# Flight_Controller_Iter2.net
KiCad netlist of a schematic drawn in EAGLE
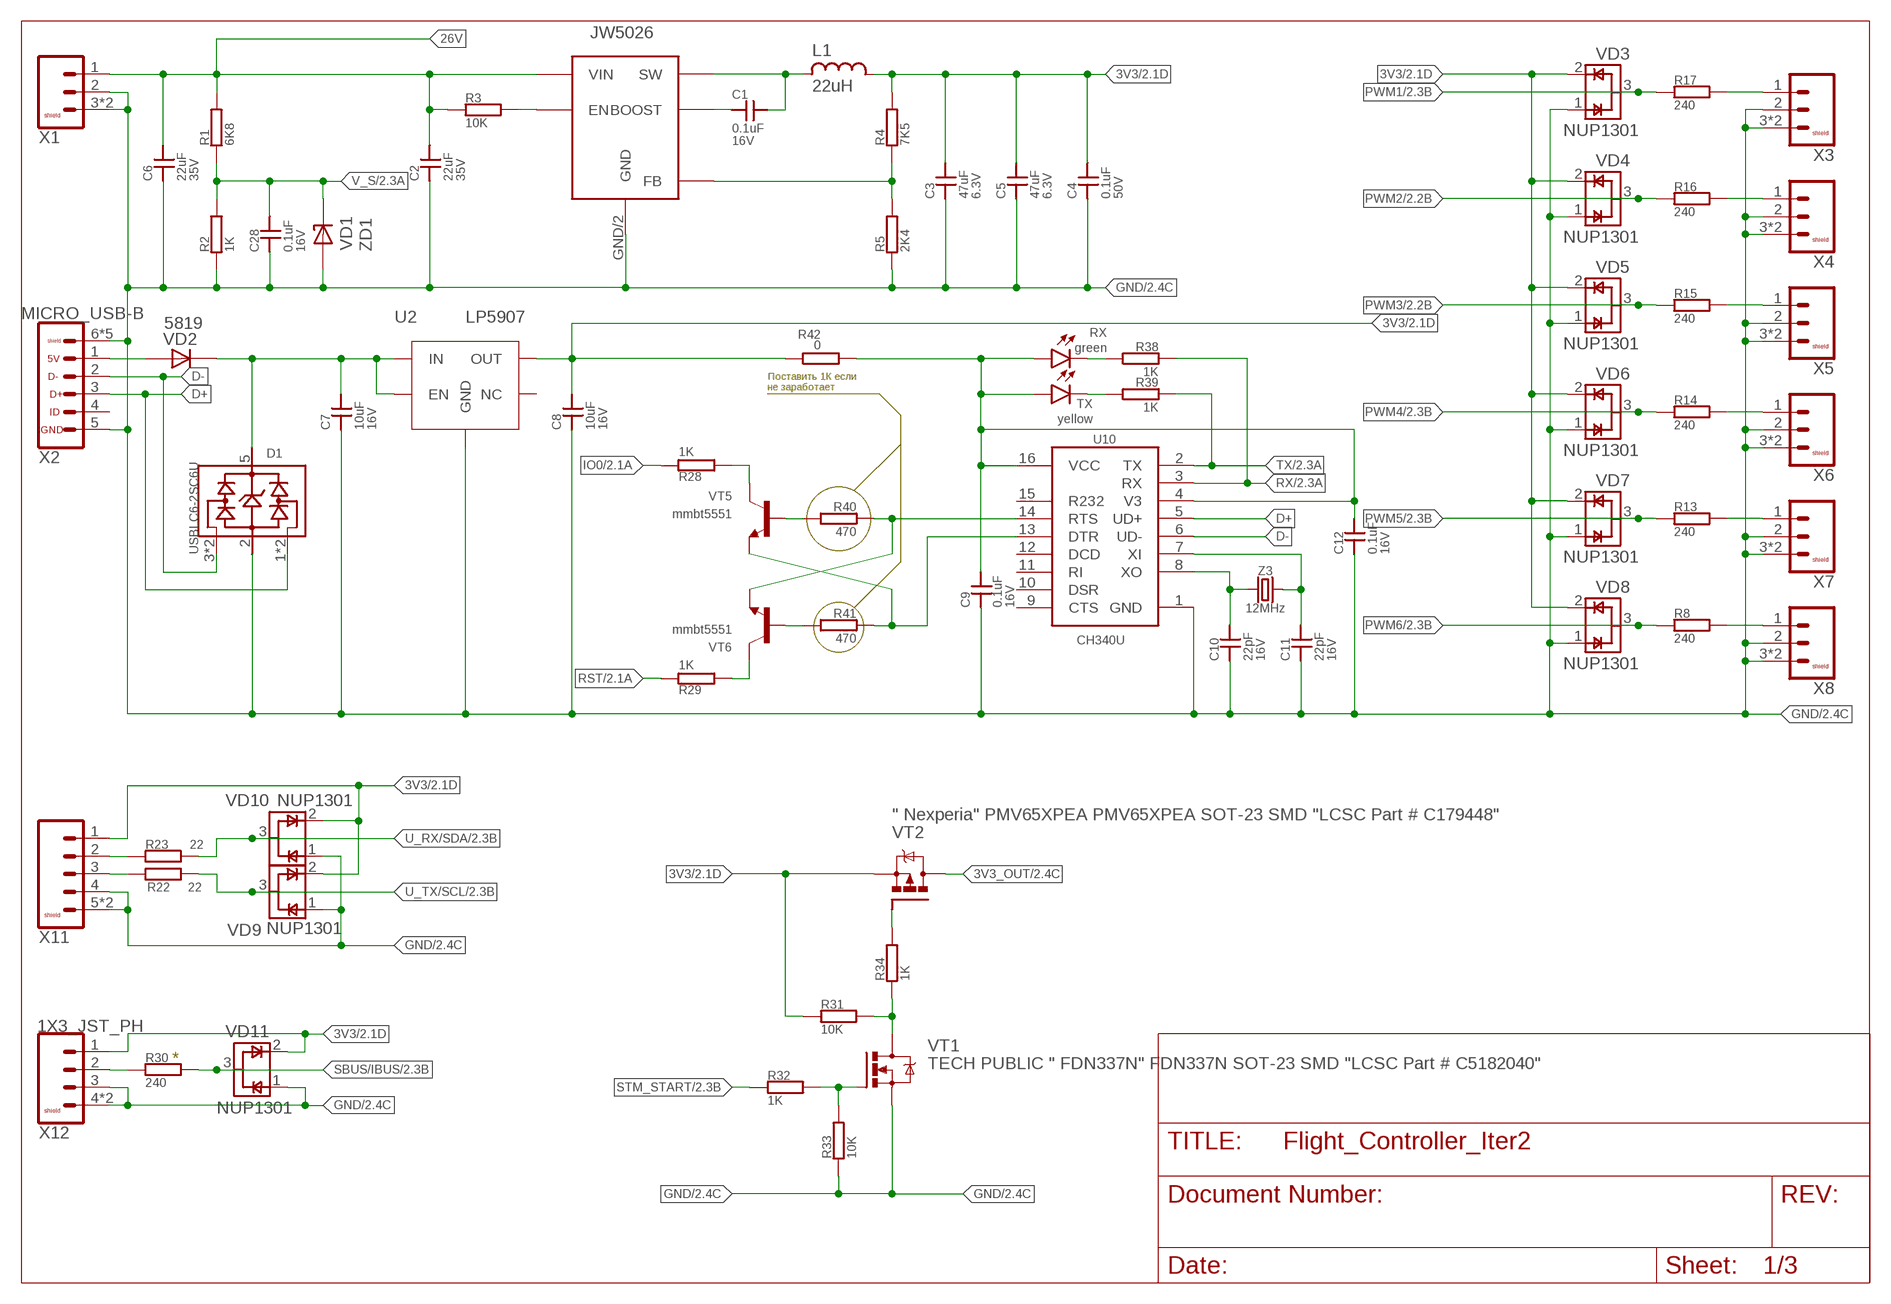
[diagram p0: schematic, sheet 1]
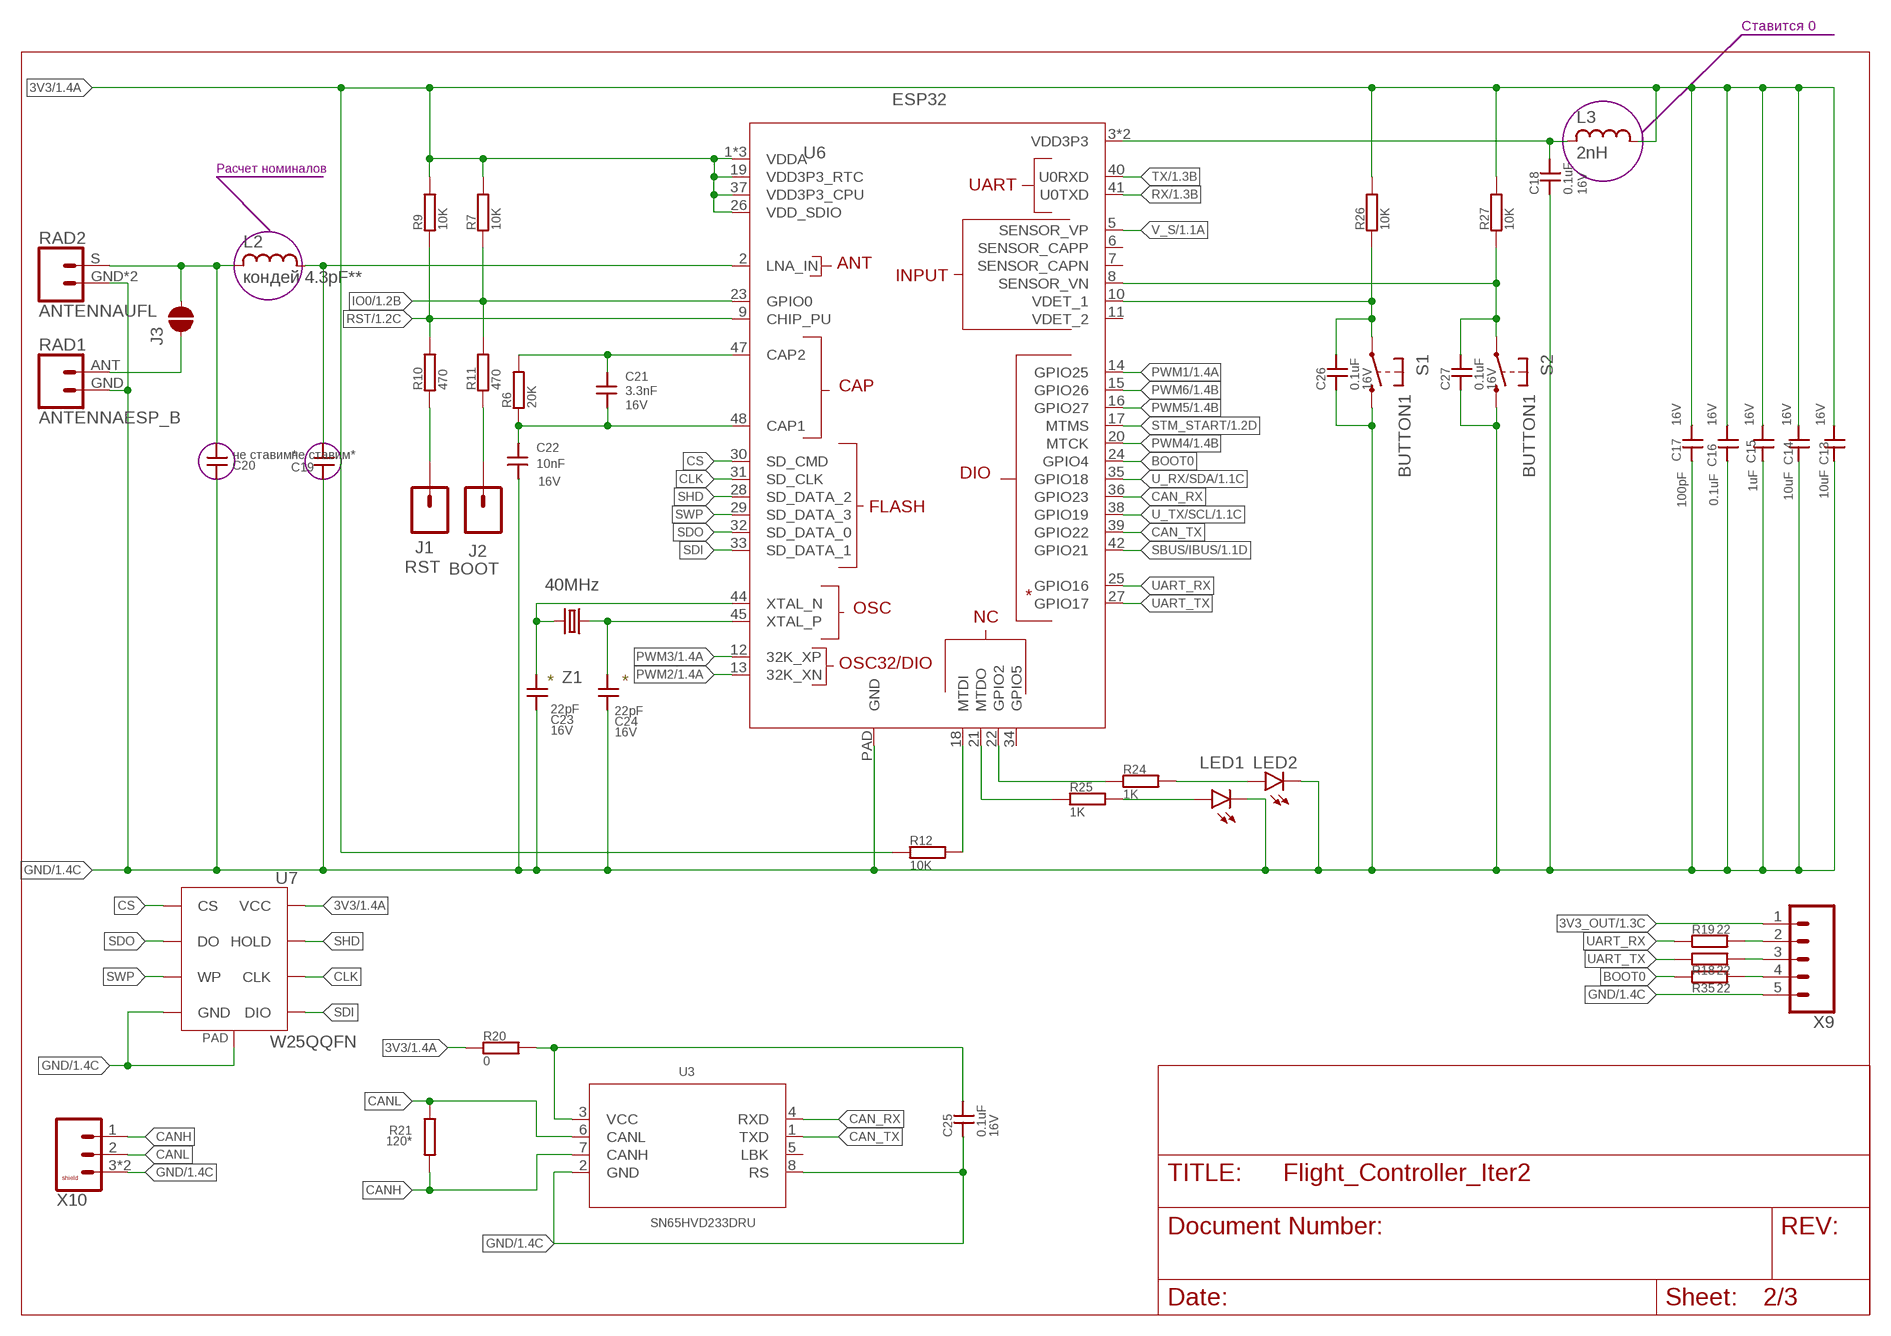
[diagram p1: schematic, sheet 2]

(export (version "E")
  (design (tool "Eeschema 10.0.6"))
  (components
    (comp (ref "C1")
      (value "0.1uF")
      (footprint "eagle-import:0402")
      (fields (field (name "VOLTAGE") "16V"))
      (libsource (lib "eagle-import") (part "C0402"))
    )
    (comp (ref "C2")
      (value "22uF")
      (footprint "eagle-import:0805")
      (fields (field (name "VOLTAGE") "35V"))
      (libsource (lib "eagle-import") (part "C0805"))
    )
    (comp (ref "C3")
      (value "47uF")
      (footprint "eagle-import:0603_SMALL")
      (fields (field (name "VOLTAGE") "6.3V"))
      (libsource (lib "eagle-import") (part "C0603_SMALL"))
    )
    (comp (ref "C4")
      (value "0.1uF")
      (footprint "eagle-import:0603_SMALL")
      (fields (field (name "VOLTAGE") "50V"))
      (libsource (lib "eagle-import") (part "C0603_SMALL"))
    )
    (comp (ref "C5")
      (value "47uF")
      (footprint "eagle-import:0603_SMALL")
      (fields (field (name "VOLTAGE") "6.3V"))
      (libsource (lib "eagle-import") (part "C0603_SMALL"))
    )
    (comp (ref "C6")
      (value "22uF")
      (footprint "eagle-import:0805")
      (fields (field (name "VOLTAGE") "35V"))
      (libsource (lib "eagle-import") (part "C0805"))
    )
    (comp (ref "C7")
      (value "10uF")
      (footprint "eagle-import:0402")
      (fields (field (name "VOLTAGE") "16V"))
      (libsource (lib "eagle-import") (part "C0402"))
    )
    (comp (ref "C8")
      (value "10uF")
      (footprint "eagle-import:0402")
      (fields (field (name "VOLTAGE") "16V"))
      (libsource (lib "eagle-import") (part "C0402"))
    )
    (comp (ref "C9")
      (value "0.1uF")
      (footprint "eagle-import:0402")
      (fields (field (name "VOLTAGE") "16V"))
      (libsource (lib "eagle-import") (part "C0402"))
    )
    (comp (ref "C10")
      (value "22pF")
      (footprint "eagle-import:0402")
      (fields (field (name "VOLTAGE") "16V"))
      (libsource (lib "eagle-import") (part "C0402"))
    )
    (comp (ref "C11")
      (value "22pF")
      (footprint "eagle-import:0402")
      (fields (field (name "VOLTAGE") "16V"))
      (libsource (lib "eagle-import") (part "C0402"))
    )
    (comp (ref "C12")
      (value "0.1uF")
      (footprint "eagle-import:0402")
      (fields (field (name "VOLTAGE") "16V"))
      (libsource (lib "eagle-import") (part "C0402"))
    )
    (comp (ref "C28")
      (value "0.1uF")
      (footprint "eagle-import:0402")
      (fields (field (name "VOLTAGE") "16V"))
      (libsource (lib "eagle-import") (part "C0402"))
    )
    (comp (ref "D1")
      (value "USBLC6-2SC6U")
      (footprint "eagle-import:SOT23-6")
      (libsource (lib "eagle-import") (part "USBLC6-2SC6U"))
    )
    (comp (ref "L1")
      (value "22uH")
      (footprint "eagle-import:0420CDMC")
      (libsource (lib "eagle-import") (part "INDUCTOR0420CDMC"))
    )
    (comp (ref "R1")
      (value "6K8")
      (footprint "eagle-import:0402")
      (libsource (lib "eagle-import") (part "R0402"))
    )
    (comp (ref "R2")
      (value "1K")
      (footprint "eagle-import:0402")
      (libsource (lib "eagle-import") (part "R0402"))
    )
    (comp (ref "R3")
      (value "10K")
      (footprint "eagle-import:0402")
      (libsource (lib "eagle-import") (part "R0402"))
    )
    (comp (ref "R4")
      (value "7K5")
      (footprint "eagle-import:0402")
      (libsource (lib "eagle-import") (part "R0402"))
    )
    (comp (ref "R5")
      (value "2K4")
      (footprint "eagle-import:0402")
      (libsource (lib "eagle-import") (part "R0402"))
    )
    (comp (ref "R8")
      (value "240")
      (footprint "eagle-import:0402")
      (libsource (lib "eagle-import") (part "R0402"))
    )
    (comp (ref "R13")
      (value "240")
      (footprint "eagle-import:0402")
      (libsource (lib "eagle-import") (part "R0402"))
    )
    (comp (ref "R14")
      (value "240")
      (footprint "eagle-import:0402")
      (libsource (lib "eagle-import") (part "R0402"))
    )
    (comp (ref "R15")
      (value "240")
      (footprint "eagle-import:0402")
      (libsource (lib "eagle-import") (part "R0402"))
    )
    (comp (ref "R16")
      (value "240")
      (footprint "eagle-import:0402")
      (libsource (lib "eagle-import") (part "R0402"))
    )
    (comp (ref "R17")
      (value "240")
      (footprint "eagle-import:0402")
      (libsource (lib "eagle-import") (part "R0402"))
    )
    (comp (ref "R22")
      (value "22")
      (footprint "eagle-import:0402")
      (libsource (lib "eagle-import") (part "R0402"))
    )
    (comp (ref "R23")
      (value "22")
      (footprint "eagle-import:0402")
      (libsource (lib "eagle-import") (part "R0402"))
    )
    (comp (ref "R28")
      (value "1K")
      (footprint "eagle-import:0402")
      (libsource (lib "eagle-import") (part "R0402"))
    )
    (comp (ref "R29")
      (value "1K")
      (footprint "eagle-import:0402")
      (libsource (lib "eagle-import") (part "R0402"))
    )
    (comp (ref "R30")
      (value "240")
      (footprint "eagle-import:0402")
      (libsource (lib "eagle-import") (part "R0402"))
    )
    (comp (ref "R31")
      (value "10K")
      (footprint "eagle-import:0402")
      (libsource (lib "eagle-import") (part "R0402"))
    )
    (comp (ref "R32")
      (value "1K")
      (footprint "eagle-import:0402")
      (libsource (lib "eagle-import") (part "R0402"))
    )
    (comp (ref "R33")
      (value "10K")
      (footprint "eagle-import:0402")
      (libsource (lib "eagle-import") (part "R0402"))
    )
    (comp (ref "R34")
      (value "1K")
      (footprint "eagle-import:0402")
      (libsource (lib "eagle-import") (part "R0402"))
    )
    (comp (ref "R38")
      (value "1K")
      (footprint "eagle-import:0402")
      (libsource (lib "eagle-import") (part "R0402"))
    )
    (comp (ref "R39")
      (value "1K")
      (footprint "eagle-import:0402")
      (libsource (lib "eagle-import") (part "R0402"))
    )
    (comp (ref "R40")
      (value "470")
      (footprint "eagle-import:0402")
      (libsource (lib "eagle-import") (part "R0402"))
    )
    (comp (ref "R41")
      (value "470")
      (footprint "eagle-import:0402")
      (libsource (lib "eagle-import") (part "R0402"))
    )
    (comp (ref "R42")
      (value "0")
      (footprint "eagle-import:0402")
      (libsource (lib "eagle-import") (part "R0402"))
    )
    (comp (ref "RX")
      (value "green")
      (footprint "eagle-import:0603")
      (libsource (lib "eagle-import") (part "LED1608"))
    )
    (comp (ref "TX")
      (value "yellow")
      (footprint "eagle-import:0603")
      (libsource (lib "eagle-import") (part "LED1608"))
    )
    (comp (ref "U1")
      (value "JW5026")
      (footprint "eagle-import:SOT-23-6")
      (libsource (lib "eagle-import") (part "TPS560430"))
    )
    (comp (ref "U2")
      (value "LP5907")
      (footprint "eagle-import:SOT-23-5")
      (libsource (lib "eagle-import") (part "LP5907"))
    )
    (comp (ref "U10")
      (value "CH340U")
      (footprint "eagle-import:SOIC-16")
      (libsource (lib "eagle-import") (part "CH340U"))
    )
    (comp (ref "VD1")
      (value "ZD1")
      (footprint "eagle-import:SOD-323")
      (libsource (lib "eagle-import") (part "ZENER-DIODES"))
    )
    (comp (ref "VD2")
      (value "5819")
      (footprint "eagle-import:SOD-323")
      (libsource (lib "eagle-import") (part "DIODE323"))
    )
    (comp (ref "VD3")
      (value "NUP1301")
      (footprint "eagle-import:SOT23")
      (libsource (lib "eagle-import") (part "ESD_PROTECTIONSOT123"))
    )
    (comp (ref "VD4")
      (value "NUP1301")
      (footprint "eagle-import:SOT23")
      (libsource (lib "eagle-import") (part "ESD_PROTECTIONSOT123"))
    )
    (comp (ref "VD5")
      (value "NUP1301")
      (footprint "eagle-import:SOT23")
      (libsource (lib "eagle-import") (part "ESD_PROTECTIONSOT123"))
    )
    (comp (ref "VD6")
      (value "NUP1301")
      (footprint "eagle-import:SOT23")
      (libsource (lib "eagle-import") (part "ESD_PROTECTIONSOT123"))
    )
    (comp (ref "VD7")
      (value "NUP1301")
      (footprint "eagle-import:SOT23")
      (libsource (lib "eagle-import") (part "ESD_PROTECTIONSOT123"))
    )
    (comp (ref "VD8")
      (value "NUP1301")
      (footprint "eagle-import:SOT23")
      (libsource (lib "eagle-import") (part "ESD_PROTECTIONSOT123"))
    )
    (comp (ref "VD9")
      (value "NUP1301")
      (footprint "eagle-import:SOT23")
      (libsource (lib "eagle-import") (part "ESD_PROTECTIONSOT123"))
    )
    (comp (ref "VD10")
      (value "NUP1301")
      (footprint "eagle-import:SOT23")
      (libsource (lib "eagle-import") (part "ESD_PROTECTIONSOT123"))
    )
    (comp (ref "VD11")
      (value "NUP1301")
      (footprint "eagle-import:SOT23")
      (libsource (lib "eagle-import") (part "ESD_PROTECTIONSOT123"))
    )
    (comp (ref "VT1")
      (value "TECH PUBLIC \" FDN337N\" FDN337N SOT-23 SMD \"LCSC Part # C5182040\"")
      (footprint "eagle-import:SOT-23")
      (libsource (lib "eagle-import") (part "N-CANNELSOT-23"))
    )
    (comp (ref "VT2")
      (value "\" Nexperia\" PMV65XPEA PMV65XPEA SOT-23 SMD \"LCSC Part # C179448\"")
      (footprint "eagle-import:SOT-23")
      (libsource (lib "eagle-import") (part "P-CANNELSOT-23"))
    )
    (comp (ref "VT5")
      (value "mmbt5551")
      (footprint "eagle-import:SOT-23")
      (libsource (lib "eagle-import") (part "NPNSOT-23"))
    )
    (comp (ref "VT6")
      (value "mmbt5551")
      (footprint "eagle-import:SOT-23")
      (libsource (lib "eagle-import") (part "NPNSOT-23"))
    )
    (comp (ref "X1")
      (value "1X2_JST_PH_LF2")
      (footprint "eagle-import:JST-PH-SM2-(LF)")
      (libsource (lib "eagle-import") (part "1X2_JST_PH_LF2"))
    )
    (comp (ref "X2")
      (value "MICRO_USB-B")
      (footprint "eagle-import:1981584-1")
      (libsource (lib "eagle-import") (part "MICRO_USB-B"))
    )
    (comp (ref "X3")
      (value "1X2_JST_PH_LF2")
      (footprint "eagle-import:JST-PH-SM2-(LF)")
      (libsource (lib "eagle-import") (part "1X2_JST_PH_LF2"))
    )
    (comp (ref "X4")
      (value "1X2_JST_PH_LF2")
      (footprint "eagle-import:JST-PH-SM2-(LF)")
      (libsource (lib "eagle-import") (part "1X2_JST_PH_LF2"))
    )
    (comp (ref "X5")
      (value "1X2_JST_PH_LF2")
      (footprint "eagle-import:JST-PH-SM2-(LF)")
      (libsource (lib "eagle-import") (part "1X2_JST_PH_LF2"))
    )
    (comp (ref "X6")
      (value "1X2_JST_PH_LF2")
      (footprint "eagle-import:JST-PH-SM2-(LF)")
      (libsource (lib "eagle-import") (part "1X2_JST_PH_LF2"))
    )
    (comp (ref "X7")
      (value "1X2_JST_PH_LF2")
      (footprint "eagle-import:JST-PH-SM2-(LF)")
      (libsource (lib "eagle-import") (part "1X2_JST_PH_LF2"))
    )
    (comp (ref "X8")
      (value "1X2_JST_PH_LF2")
      (footprint "eagle-import:JST-PH-SM2-(LF)")
      (libsource (lib "eagle-import") (part "1X2_JST_PH_LF2"))
    )
    (comp (ref "X11")
      (value "1X4_JST_PH_2JST_PH_SM4_2MM(LF)")
      (footprint "eagle-import:JST-PH-SM4-(LF)")
      (libsource (lib "eagle-import") (part "1X4_JST_PH_2JST_PH_SM4_2MM(LF)"))
    )
    (comp (ref "X12")
      (value "1X3_JST_PH")
      (footprint "eagle-import:JST-PH-SM3-(LF)")
      (libsource (lib "eagle-import") (part "1X3_JST_PH"))
    )
    (comp (ref "Z3")
      (value "12MHz")
      (footprint "eagle-import:CRYSTAL-SMD-3.2X2.5MM")
      (libsource (lib "eagle-import") (part "CRYSTAL4FOOT"))
    )
    (comp (ref "C13")
      (value "10uF")
      (footprint "eagle-import:0402")
      (fields (field (name "VOLTAGE") "16V"))
      (libsource (lib "eagle-import") (part "C0402"))
    )
    (comp (ref "C14")
      (value "10uF")
      (footprint "eagle-import:0402")
      (fields (field (name "VOLTAGE") "16V"))
      (libsource (lib "eagle-import") (part "C0402"))
    )
    (comp (ref "C15")
      (value "1uF")
      (footprint "eagle-import:0402")
      (fields (field (name "VOLTAGE") "16V"))
      (libsource (lib "eagle-import") (part "C0402"))
    )
    (comp (ref "C16")
      (value "0.1uF")
      (footprint "eagle-import:0402")
      (fields (field (name "VOLTAGE") "16V"))
      (libsource (lib "eagle-import") (part "C0402"))
    )
    (comp (ref "C17")
      (value "100pF")
      (footprint "eagle-import:0402")
      (fields (field (name "VOLTAGE") "16V"))
      (libsource (lib "eagle-import") (part "C0402"))
    )
    (comp (ref "C18")
      (value "0.1uF")
      (footprint "eagle-import:0402")
      (fields (field (name "VOLTAGE") "16V"))
      (libsource (lib "eagle-import") (part "C0402"))
    )
    (comp (ref "C19")
      (value "не ставим*")
      (footprint "eagle-import:0402")
      (libsource (lib "eagle-import") (part "C0402"))
    )
    (comp (ref "C20")
      (value "не ставим*")
      (footprint "eagle-import:0402")
      (libsource (lib "eagle-import") (part "C0402"))
    )
    (comp (ref "C21")
      (value "3.3nF")
      (footprint "eagle-import:0402")
      (fields (field (name "VOLTAGE") "16V"))
      (libsource (lib "eagle-import") (part "C0402"))
    )
    (comp (ref "C22")
      (value "10nF")
      (footprint "eagle-import:0402")
      (fields (field (name "VOLTAGE") "16V"))
      (libsource (lib "eagle-import") (part "C0402"))
    )
    (comp (ref "C23")
      (value "22pF")
      (footprint "eagle-import:0402")
      (fields (field (name "VOLTAGE") "16V"))
      (libsource (lib "eagle-import") (part "C0402"))
    )
    (comp (ref "C24")
      (value "22pF")
      (footprint "eagle-import:0402")
      (fields (field (name "VOLTAGE") "16V"))
      (libsource (lib "eagle-import") (part "C0402"))
    )
    (comp (ref "C25")
      (value "0.1uF")
      (footprint "eagle-import:0402")
      (fields (field (name "VOLTAGE") "16V"))
      (libsource (lib "eagle-import") (part "C0402"))
    )
    (comp (ref "C26")
      (value "0.1uF")
      (footprint "eagle-import:0402")
      (fields (field (name "VOLTAGE") "16V"))
      (libsource (lib "eagle-import") (part "C0402"))
    )
    (comp (ref "C27")
      (value "0.1uF")
      (footprint "eagle-import:0402")
      (fields (field (name "VOLTAGE") "16V"))
      (libsource (lib "eagle-import") (part "C0402"))
    )
    (comp (ref "J1")
      (value "RST")
      (footprint "eagle-import:1X1_PAD_T")
      (libsource (lib "eagle-import") (part "1X1_PAD1X1PAD"))
    )
    (comp (ref "J2")
      (value "BOOT")
      (footprint "eagle-import:1X1_PAD_T")
      (libsource (lib "eagle-import") (part "1X1_PAD1X1PAD"))
    )
    (comp (ref "J3")
      (value "TEST_PAD1X1MM")
      (footprint "eagle-import:TEST_PAD")
      (libsource (lib "eagle-import") (part "TEST_PAD1X1MM"))
    )
    (comp (ref "L2")
      (value "кондей 4.3pF**")
      (footprint "eagle-import:0402")
      (libsource (lib "eagle-import") (part "L0402"))
    )
    (comp (ref "L3")
      (value "2nH")
      (footprint "eagle-import:0402")
      (libsource (lib "eagle-import") (part "L0402"))
    )
    (comp (ref "LED1")
      (value "LED0402")
      (footprint "eagle-import:0402")
      (libsource (lib "eagle-import") (part "LED0402"))
    )
    (comp (ref "LED2")
      (value "LED0402")
      (footprint "eagle-import:0402")
      (libsource (lib "eagle-import") (part "LED0402"))
    )
    (comp (ref "R6")
      (value "20K")
      (footprint "eagle-import:0402")
      (libsource (lib "eagle-import") (part "R0402"))
    )
    (comp (ref "R7")
      (value "10K")
      (footprint "eagle-import:0402")
      (libsource (lib "eagle-import") (part "R0402"))
    )
    (comp (ref "R9")
      (value "10K")
      (footprint "eagle-import:0402")
      (libsource (lib "eagle-import") (part "R0402"))
    )
    (comp (ref "R10")
      (value "470")
      (footprint "eagle-import:0402")
      (libsource (lib "eagle-import") (part "R0402"))
    )
    (comp (ref "R11")
      (value "470")
      (footprint "eagle-import:0402")
      (libsource (lib "eagle-import") (part "R0402"))
    )
    (comp (ref "R12")
      (value "10K")
      (footprint "eagle-import:0402")
      (libsource (lib "eagle-import") (part "R0402"))
    )
    (comp (ref "R18")
      (value "22")
      (footprint "eagle-import:0402")
      (libsource (lib "eagle-import") (part "R0402"))
    )
    (comp (ref "R19")
      (value "22")
      (footprint "eagle-import:0402")
      (libsource (lib "eagle-import") (part "R0402"))
    )
    (comp (ref "R20")
      (value "0")
      (footprint "eagle-import:0402")
      (libsource (lib "eagle-import") (part "R0402"))
    )
    (comp (ref "R21")
      (value "120*")
      (footprint "eagle-import:0603_SMALL")
      (libsource (lib "eagle-import") (part "R0603_SMALL"))
    )
    (comp (ref "R24")
      (value "1K")
      (footprint "eagle-import:0402")
      (libsource (lib "eagle-import") (part "R0402"))
    )
    (comp (ref "R25")
      (value "1K")
      (footprint "eagle-import:0402")
      (libsource (lib "eagle-import") (part "R0402"))
    )
    (comp (ref "R26")
      (value "10K")
      (footprint "eagle-import:0402")
      (libsource (lib "eagle-import") (part "R0402"))
    )
    (comp (ref "R27")
      (value "10K")
      (footprint "eagle-import:0402")
      (libsource (lib "eagle-import") (part "R0402"))
    )
    (comp (ref "R35")
      (value "22")
      (footprint "eagle-import:0402")
      (libsource (lib "eagle-import") (part "R0402"))
    )
    (comp (ref "RAD1")
      (value "ANTENNAESP_B")
      (footprint "eagle-import:2.4GHZB")
      (libsource (lib "eagle-import") (part "ANTENNAESP_B"))
    )
    (comp (ref "RAD2")
      (value "ANTENNAUFL")
      (footprint "eagle-import:U.FL")
      (libsource (lib "eagle-import") (part "ANTENNAUFL"))
    )
    (comp (ref "S1")
      (value "BUTTON1")
      (footprint "eagle-import:3X4X2")
      (libsource (lib "eagle-import") (part "BUTTON1"))
    )
    (comp (ref "S2")
      (value "BUTTON1")
      (footprint "eagle-import:3X4X2")
      (libsource (lib "eagle-import") (part "BUTTON1"))
    )
    (comp (ref "U3")
      (value "SN65HVD233DRU")
      (footprint "eagle-import:SOIC-8")
      (libsource (lib "eagle-import") (part "SN65HVD233DRU"))
    )
    (comp (ref "U6")
      (value "ESP32")
      (footprint "eagle-import:QFN48(5X5MM)")
      (libsource (lib "eagle-import") (part "ESP32"))
    )
    (comp (ref "U7")
      (value "W25QQFN")
      (footprint "eagle-import:WSON8X6-MM")
      (libsource (lib "eagle-import") (part "W25QQFN"))
    )
    (comp (ref "X9")
      (value "1X5FFC5-1MM")
      (footprint "eagle-import:FFC-1MM_5")
      (libsource (lib "eagle-import") (part "1X5FFC5-1MM"))
    )
    (comp (ref "X10")
      (value "1X2_JST_PH_LF2")
      (footprint "eagle-import:JST-PH-SM2-(LF)")
      (libsource (lib "eagle-import") (part "1X2_JST_PH_LF2"))
    )
    (comp (ref "Z1")
      (value "40MHz")
      (footprint "eagle-import:CRYSTAL-SMD-3.2X2.5MM")
      (libsource (lib "eagle-import") (part "CRYSTAL4FOOT"))
    )
  )
  (nets
    (net (code "1") (name "3V3") (class "Default")
      (node (ref "C13") (pin "2") (pinfunction "P$2_2") (pintype "bidirectional"))
      (node (ref "C14") (pin "2") (pinfunction "P$2_2") (pintype "bidirectional"))
      (node (ref "C15") (pin "2") (pinfunction "P$2_2") (pintype "bidirectional"))
      (node (ref "C16") (pin "2") (pinfunction "P$2_2") (pintype "bidirectional"))
      (node (ref "C17") (pin "2") (pinfunction "P$2_2") (pintype "bidirectional"))
      (node (ref "C3") (pin "P$2") (pinfunction "P$2_P$2") (pintype "bidirectional"))
      (node (ref "C4") (pin "P$2") (pinfunction "P$2_P$2") (pintype "bidirectional"))
      (node (ref "C5") (pin "P$2") (pinfunction "P$2_P$2") (pintype "bidirectional"))
      (node (ref "C8") (pin "2") (pinfunction "P$2_2") (pintype "bidirectional"))
      (node (ref "L1") (pin "2") (pinfunction "2_2") (pintype "passive"))
      (node (ref "L3") (pin "2") (pinfunction "2_2") (pintype "passive"))
      (node (ref "R12") (pin "1") (pinfunction "P$1_1") (pintype "bidirectional"))
      (node (ref "R20") (pin "1") (pinfunction "P$1_1") (pintype "bidirectional"))
      (node (ref "R26") (pin "2") (pinfunction "P$2_2") (pintype "bidirectional"))
      (node (ref "R27") (pin "2") (pinfunction "P$2_2") (pintype "bidirectional"))
      (node (ref "R31") (pin "1") (pinfunction "P$1_1") (pintype "bidirectional"))
      (node (ref "R4") (pin "2") (pinfunction "P$2_2") (pintype "bidirectional"))
      (node (ref "R42") (pin "2") (pinfunction "P$2_2") (pintype "bidirectional"))
      (node (ref "R7") (pin "2") (pinfunction "P$2_2") (pintype "bidirectional"))
      (node (ref "R9") (pin "2") (pinfunction "P$2_2") (pintype "bidirectional"))
      (node (ref "U2") (pin "5") (pinfunction "OUT_5") (pintype "bidirectional"))
      (node (ref "U6") (pin "1") (pinfunction "VDDA_1") (pintype "bidirectional"))
      (node (ref "U6") (pin "19") (pinfunction "VDD3P3_RTC_19") (pintype "bidirectional"))
      (node (ref "U6") (pin "26") (pinfunction "VDD_SDIO_26") (pintype "bidirectional"))
      (node (ref "U6") (pin "37") (pinfunction "VDD3P3_CPU_37") (pintype "bidirectional"))
      (node (ref "U6") (pin "43") (pinfunction "VDDA_43") (pintype "bidirectional"))
      (node (ref "U6") (pin "46") (pinfunction "VDDA_46") (pintype "bidirectional"))
      (node (ref "U7") (pin "P$9") (pinfunction "VCC_P$9") (pintype "bidirectional"))
      (node (ref "VD10") (pin "2") (pinfunction "VCC_2") (pintype "bidirectional"))
      (node (ref "VD11") (pin "2") (pinfunction "VCC_2") (pintype "bidirectional"))
      (node (ref "VD3") (pin "2") (pinfunction "VCC_2") (pintype "bidirectional"))
      (node (ref "VD4") (pin "2") (pinfunction "VCC_2") (pintype "bidirectional"))
      (node (ref "VD5") (pin "2") (pinfunction "VCC_2") (pintype "bidirectional"))
      (node (ref "VD6") (pin "2") (pinfunction "VCC_2") (pintype "bidirectional"))
      (node (ref "VD7") (pin "2") (pinfunction "VCC_2") (pintype "bidirectional"))
      (node (ref "VD8") (pin "2") (pinfunction "VCC_2") (pintype "bidirectional"))
      (node (ref "VD9") (pin "2") (pinfunction "VCC_2") (pintype "bidirectional"))
      (node (ref "VT2") (pin "2") (pinfunction "S_2") (pintype "passive"))
      (node (ref "X11") (pin "1") (pinfunction "1_1") (pintype "passive"))
      (node (ref "X12") (pin "1") (pinfunction "1_1") (pintype "passive"))
    )
    (net (code "2") (name "3V3_OUT") (class "Default")
      (node (ref "VT2") (pin "3") (pinfunction "D_3") (pintype "passive"))
      (node (ref "X9") (pin "1") (pinfunction "1_1") (pintype "passive"))
    )
    (net (code "3") (name "26V") (class "Default")
      (node (ref "C2") (pin "P$2") (pinfunction "P$2_P$2") (pintype "bidirectional"))
      (node (ref "C6") (pin "P$2") (pinfunction "P$2_P$2") (pintype "bidirectional"))
      (node (ref "R1") (pin "2") (pinfunction "P$2_2") (pintype "bidirectional"))
      (node (ref "R3") (pin "1") (pinfunction "P$1_1") (pintype "bidirectional"))
      (node (ref "U1") (pin "IN/5") (pinfunction "VIN_IN/5") (pintype "input"))
      (node (ref "X1") (pin "1") (pinfunction "1_1") (pintype "passive"))
    )
    (net (code "4") (name "BOOT0") (class "Default")
      (node (ref "R35") (pin "1") (pinfunction "P$1_1") (pintype "bidirectional"))
      (node (ref "U6") (pin "24") (pinfunction "GPIO4_24") (pintype "bidirectional"))
    )
    (net (code "5") (name "CANH") (class "Default")
      (node (ref "R21") (pin "P$1") (pinfunction "P$1_P$1") (pintype "bidirectional"))
      (node (ref "U3") (pin "7") (pinfunction "CANH_7") (pintype "bidirectional"))
      (node (ref "X10") (pin "1") (pinfunction "1_1") (pintype "passive"))
    )
    (net (code "6") (name "CANL") (class "Default")
      (node (ref "R21") (pin "P$2") (pinfunction "P$2_P$2") (pintype "bidirectional"))
      (node (ref "U3") (pin "6") (pinfunction "CANL_6") (pintype "bidirectional"))
      (node (ref "X10") (pin "2") (pinfunction "2_2") (pintype "passive"))
    )
    (net (code "7") (name "CAN_RX") (class "Default")
      (node (ref "U3") (pin "4") (pinfunction "RXD_4") (pintype "bidirectional"))
      (node (ref "U6") (pin "36") (pinfunction "GPIO23_36") (pintype "bidirectional"))
    )
    (net (code "8") (name "CAN_TX") (class "Default")
      (node (ref "U3") (pin "1") (pinfunction "TXD_1") (pintype "bidirectional"))
      (node (ref "U6") (pin "39") (pinfunction "GPIO22_39") (pintype "bidirectional"))
    )
    (net (code "9") (name "CLK") (class "Default")
      (node (ref "U6") (pin "31") (pinfunction "SD_CLK_31") (pintype "bidirectional"))
      (node (ref "U7") (pin "P$7") (pinfunction "CLK_P$7") (pintype "bidirectional"))
    )
    (net (code "10") (name "CS") (class "Default")
      (node (ref "U6") (pin "30") (pinfunction "SD_CMD_30") (pintype "bidirectional"))
      (node (ref "U7") (pin "P$2") (pinfunction "CS_P$2") (pintype "bidirectional"))
    )
    (net (code "11") (name "D+") (class "Default")
      (node (ref "D1") (pin "1") (pinfunction "I/O1_1") (pintype "bidirectional"))
      (node (ref "D1") (pin "6") (pinfunction "I/O1_6") (pintype "bidirectional"))
      (node (ref "U10") (pin "5") (pinfunction "UD+_5") (pintype "bidirectional"))
      (node (ref "X2") (pin "3") (pinfunction "D+_3") (pintype "passive"))
    )
    (net (code "12") (name "D-") (class "Default")
      (node (ref "D1") (pin "3") (pinfunction "I/O2_3") (pintype "bidirectional"))
      (node (ref "D1") (pin "4") (pinfunction "I/O2_4") (pintype "bidirectional"))
      (node (ref "U10") (pin "6") (pinfunction "UD-_6") (pintype "bidirectional"))
      (node (ref "X2") (pin "2") (pinfunction "D-_2") (pintype "passive"))
    )
    (net (code "13") (name "GND") (class "Default")
      (node (ref "C10") (pin "1") (pinfunction "P$1_1") (pintype "bidirectional"))
      (node (ref "C11") (pin "1") (pinfunction "P$1_1") (pintype "bidirectional"))
      (node (ref "C12") (pin "1") (pinfunction "P$1_1") (pintype "bidirectional"))
      (node (ref "C13") (pin "1") (pinfunction "P$1_1") (pintype "bidirectional"))
      (node (ref "C14") (pin "1") (pinfunction "P$1_1") (pintype "bidirectional"))
      (node (ref "C15") (pin "1") (pinfunction "P$1_1") (pintype "bidirectional"))
      (node (ref "C16") (pin "1") (pinfunction "P$1_1") (pintype "bidirectional"))
      (node (ref "C17") (pin "1") (pinfunction "P$1_1") (pintype "bidirectional"))
      (node (ref "C18") (pin "1") (pinfunction "P$1_1") (pintype "bidirectional"))
      (node (ref "C19") (pin "1") (pinfunction "P$1_1") (pintype "bidirectional"))
      (node (ref "C2") (pin "P$1") (pinfunction "P$1_P$1") (pintype "bidirectional"))
      (node (ref "C20") (pin "1") (pinfunction "P$1_1") (pintype "bidirectional"))
      (node (ref "C22") (pin "1") (pinfunction "P$1_1") (pintype "bidirectional"))
      (node (ref "C23") (pin "1") (pinfunction "P$1_1") (pintype "bidirectional"))
      (node (ref "C24") (pin "1") (pinfunction "P$1_1") (pintype "bidirectional"))
      (node (ref "C25") (pin "1") (pinfunction "P$1_1") (pintype "bidirectional"))
      (node (ref "C26") (pin "1") (pinfunction "P$1_1") (pintype "bidirectional"))
      (node (ref "C27") (pin "1") (pinfunction "P$1_1") (pintype "bidirectional"))
      (node (ref "C28") (pin "1") (pinfunction "P$1_1") (pintype "bidirectional"))
      (node (ref "C3") (pin "P$1") (pinfunction "P$1_P$1") (pintype "bidirectional"))
      (node (ref "C4") (pin "P$1") (pinfunction "P$1_P$1") (pintype "bidirectional"))
      (node (ref "C5") (pin "P$1") (pinfunction "P$1_P$1") (pintype "bidirectional"))
      (node (ref "C6") (pin "P$1") (pinfunction "P$1_P$1") (pintype "bidirectional"))
      (node (ref "C7") (pin "1") (pinfunction "P$1_1") (pintype "bidirectional"))
      (node (ref "C8") (pin "1") (pinfunction "P$1_1") (pintype "bidirectional"))
      (node (ref "C9") (pin "1") (pinfunction "P$1_1") (pintype "bidirectional"))
      (node (ref "D1") (pin "2") (pinfunction "GND_2") (pintype "power_in"))
      (node (ref "LED1") (pin "1") (pinfunction "C_1") (pintype "passive"))
      (node (ref "LED2") (pin "1") (pinfunction "C_1") (pintype "passive"))
      (node (ref "R2") (pin "1") (pinfunction "P$1_1") (pintype "bidirectional"))
      (node (ref "R33") (pin "1") (pinfunction "P$1_1") (pintype "bidirectional"))
      (node (ref "R5") (pin "1") (pinfunction "P$1_1") (pintype "bidirectional"))
      (node (ref "RAD1") (pin "GND") (pinfunction "GND_GND") (pintype "passive"))
      (node (ref "RAD2") (pin "GND") (pinfunction "GND_GND") (pintype "passive"))
      (node (ref "RAD2") (pin "GND1") (pinfunction "GND_GND1") (pintype "passive"))
      (node (ref "S1") (pin "P$2") (pinfunction "4_P$2") (pintype "passive"))
      (node (ref "S2") (pin "P$2") (pinfunction "4_P$2") (pintype "passive"))
      (node (ref "U1") (pin "GND/2") (pinfunction "GND_GND/2") (pintype "output"))
      (node (ref "U10") (pin "1") (pinfunction "GND_1") (pintype "power_in"))
      (node (ref "U2") (pin "2") (pinfunction "GND_2") (pintype "bidirectional"))
      (node (ref "U3") (pin "2") (pinfunction "GND_2") (pintype "bidirectional"))
      (node (ref "U3") (pin "8") (pinfunction "RS_8") (pintype "bidirectional"))
      (node (ref "U6") (pin "PAD") (pinfunction "GND_PAD") (pintype "bidirectional"))
      (node (ref "U7") (pin "P$1") (pinfunction "P$1_P$1") (pintype "bidirectional"))
      (node (ref "U7") (pin "P$5") (pinfunction "GND_P$5") (pintype "bidirectional"))
      (node (ref "VD1") (pin "1") (pinfunction "A_1") (pintype "passive"))
      (node (ref "VD10") (pin "1") (pinfunction "GND_1") (pintype "bidirectional"))
      (node (ref "VD11") (pin "1") (pinfunction "GND_1") (pintype "bidirectional"))
      (node (ref "VD3") (pin "1") (pinfunction "GND_1") (pintype "bidirectional"))
      (node (ref "VD4") (pin "1") (pinfunction "GND_1") (pintype "bidirectional"))
      (node (ref "VD5") (pin "1") (pinfunction "GND_1") (pintype "bidirectional"))
      (node (ref "VD6") (pin "1") (pinfunction "GND_1") (pintype "bidirectional"))
      (node (ref "VD7") (pin "1") (pinfunction "GND_1") (pintype "bidirectional"))
      (node (ref "VD8") (pin "1") (pinfunction "GND_1") (pintype "bidirectional"))
      (node (ref "VD9") (pin "1") (pinfunction "GND_1") (pintype "bidirectional"))
      (node (ref "VT1") (pin "2") (pinfunction "S_2") (pintype "passive"))
      (node (ref "X1") (pin "2") (pinfunction "2_2") (pintype "passive"))
      (node (ref "X1") (pin "3") (pinfunction "3_3") (pintype "passive"))
      (node (ref "X1") (pin "4") (pinfunction "3_4") (pintype "passive"))
      (node (ref "X10") (pin "3") (pinfunction "3_3") (pintype "passive"))
      (node (ref "X10") (pin "4") (pinfunction "3_4") (pintype "passive"))
      (node (ref "X11") (pin "4") (pinfunction "4_4") (pintype "passive"))
      (node (ref "X11") (pin "5") (pinfunction "5_5") (pintype "passive"))
      (node (ref "X11") (pin "6") (pinfunction "5_6") (pintype "passive"))
      (node (ref "X12") (pin "3") (pinfunction "3_3") (pintype "passive"))
      (node (ref "X12") (pin "4") (pinfunction "4_4") (pintype "passive"))
      (node (ref "X12") (pin "5") (pinfunction "4_5") (pintype "passive"))
      (node (ref "X2") (pin "5") (pinfunction "GND_5") (pintype "passive"))
      (node (ref "X2") (pin "6") (pinfunction "SHIELD_6") (pintype "passive"))
      (node (ref "X2") (pin "P$1") (pinfunction "SHIELD_P$1") (pintype "passive"))
      (node (ref "X2") (pin "P$2") (pinfunction "SHIELD_P$2") (pintype "passive"))
      (node (ref "X2") (pin "P$3") (pinfunction "SHIELD_P$3") (pintype "passive"))
      (node (ref "X2") (pin "P$7") (pinfunction "SHIELD_P$7") (pintype "passive"))
      (node (ref "X3") (pin "2") (pinfunction "2_2") (pintype "passive"))
      (node (ref "X3") (pin "3") (pinfunction "3_3") (pintype "passive"))
      (node (ref "X3") (pin "4") (pinfunction "3_4") (pintype "passive"))
      (node (ref "X4") (pin "2") (pinfunction "2_2") (pintype "passive"))
      (node (ref "X4") (pin "3") (pinfunction "3_3") (pintype "passive"))
      (node (ref "X4") (pin "4") (pinfunction "3_4") (pintype "passive"))
      (node (ref "X5") (pin "2") (pinfunction "2_2") (pintype "passive"))
      (node (ref "X5") (pin "3") (pinfunction "3_3") (pintype "passive"))
      (node (ref "X5") (pin "4") (pinfunction "3_4") (pintype "passive"))
      (node (ref "X6") (pin "2") (pinfunction "2_2") (pintype "passive"))
      (node (ref "X6") (pin "3") (pinfunction "3_3") (pintype "passive"))
      (node (ref "X6") (pin "4") (pinfunction "3_4") (pintype "passive"))
      (node (ref "X7") (pin "2") (pinfunction "2_2") (pintype "passive"))
      (node (ref "X7") (pin "3") (pinfunction "3_3") (pintype "passive"))
      (node (ref "X7") (pin "4") (pinfunction "3_4") (pintype "passive"))
      (node (ref "X8") (pin "2") (pinfunction "2_2") (pintype "passive"))
      (node (ref "X8") (pin "3") (pinfunction "3_3") (pintype "passive"))
      (node (ref "X8") (pin "4") (pinfunction "3_4") (pintype "passive"))
      (node (ref "X9") (pin "5") (pinfunction "5_5") (pintype "passive"))
    )
    (net (code "14") (name "IO0") (class "Default")
      (node (ref "R11") (pin "2") (pinfunction "P$2_2") (pintype "bidirectional"))
      (node (ref "R28") (pin "1") (pinfunction "P$1_1") (pintype "bidirectional"))
      (node (ref "R7") (pin "1") (pinfunction "P$1_1") (pintype "bidirectional"))
      (node (ref "U6") (pin "23") (pinfunction "GPIO0_23") (pintype "bidirectional"))
    )
    (net (code "15") (name "Net-(C1-P$1)") (class "Default")
      (node (ref "C1") (pin "1") (pinfunction "P$1_1") (pintype "bidirectional"))
      (node (ref "U1") (pin "BOOST/1") (pinfunction "BOOST_BOOST/1") (pintype "output"))
    )
    (net (code "16") (name "Net-(C1-P$2)") (class "Default")
      (node (ref "C1") (pin "2") (pinfunction "P$2_2") (pintype "bidirectional"))
      (node (ref "L1") (pin "1") (pinfunction "1_1") (pintype "passive"))
      (node (ref "U1") (pin "SW/6") (pinfunction "SW_SW/6") (pintype "output"))
    )
    (net (code "17") (name "Net-(C7-P$2)") (class "Default")
      (node (ref "C7") (pin "2") (pinfunction "P$2_2") (pintype "bidirectional"))
      (node (ref "D1") (pin "5") (pinfunction "VBUS_5") (pintype "power_in"))
      (node (ref "U2") (pin "1") (pinfunction "IN_1") (pintype "bidirectional"))
      (node (ref "U2") (pin "3") (pinfunction "EN_3") (pintype "bidirectional"))
      (node (ref "VD2") (pin "2") (pinfunction "C_2") (pintype "passive"))
    )
    (net (code "18") (name "Net-(C10-P$2)") (class "Default")
      (node (ref "C10") (pin "2") (pinfunction "P$2_2") (pintype "bidirectional"))
      (node (ref "U10") (pin "8") (pinfunction "XO_8") (pintype "output"))
      (node (ref "Z3") (pin "3") (pinfunction "2_3") (pintype "passive"))
    )
    (net (code "19") (name "Net-(C11-P$2)") (class "Default")
      (node (ref "C11") (pin "2") (pinfunction "P$2_2") (pintype "bidirectional"))
      (node (ref "U10") (pin "7") (pinfunction "XI_7") (pintype "input"))
      (node (ref "Z3") (pin "1") (pinfunction "1_1") (pintype "passive"))
    )
    (net (code "20") (name "Net-(C12-P$2)") (class "Default")
      (node (ref "C12") (pin "2") (pinfunction "P$2_2") (pintype "bidirectional"))
      (node (ref "C9") (pin "2") (pinfunction "P$2_2") (pintype "bidirectional"))
      (node (ref "R42") (pin "1") (pinfunction "P$1_1") (pintype "bidirectional"))
      (node (ref "RX") (pin "P$2") (pinfunction "A_P$2") (pintype "passive"))
      (node (ref "TX") (pin "P$2") (pinfunction "A_P$2") (pintype "passive"))
      (node (ref "U10") (pin "16") (pinfunction "VCC_16") (pintype "power_in"))
      (node (ref "U10") (pin "4") (pinfunction "V3_4") (pintype "power_in"))
    )
    (net (code "21") (name "Net-(C18-P$2)") (class "Default")
      (node (ref "C18") (pin "2") (pinfunction "P$2_2") (pintype "bidirectional"))
      (node (ref "L3") (pin "1") (pinfunction "1_1") (pintype "passive"))
      (node (ref "U6") (pin "3") (pinfunction "VDD3P3_3") (pintype "bidirectional"))
      (node (ref "U6") (pin "4") (pinfunction "VDD3P3_4") (pintype "bidirectional"))
    )
    (net (code "22") (name "Net-(C19-P$2)") (class "Default")
      (node (ref "C19") (pin "2") (pinfunction "P$2_2") (pintype "bidirectional"))
      (node (ref "L2") (pin "2") (pinfunction "2_2") (pintype "passive"))
      (node (ref "U6") (pin "2") (pinfunction "LNA_IN_2") (pintype "bidirectional"))
    )
    (net (code "23") (name "Net-(C20-P$2)") (class "Default")
      (node (ref "C20") (pin "2") (pinfunction "P$2_2") (pintype "bidirectional"))
      (node (ref "J3") (pin "P$2") (pinfunction "P$2_P$2") (pintype "bidirectional"))
      (node (ref "L2") (pin "1") (pinfunction "1_1") (pintype "passive"))
      (node (ref "RAD2") (pin "S") (pinfunction "ANTENNA_S") (pintype "passive"))
    )
    (net (code "24") (name "Net-(C21-P$1)") (class "Default")
      (node (ref "C21") (pin "1") (pinfunction "P$1_1") (pintype "bidirectional"))
      (node (ref "C22") (pin "2") (pinfunction "P$2_2") (pintype "bidirectional"))
      (node (ref "R6") (pin "1") (pinfunction "P$1_1") (pintype "bidirectional"))
      (node (ref "U6") (pin "48") (pinfunction "CAP1_48") (pintype "bidirectional"))
    )
    (net (code "25") (name "Net-(C21-P$2)") (class "Default")
      (node (ref "C21") (pin "2") (pinfunction "P$2_2") (pintype "bidirectional"))
      (node (ref "R6") (pin "2") (pinfunction "P$2_2") (pintype "bidirectional"))
      (node (ref "U6") (pin "47") (pinfunction "CAP2_47") (pintype "bidirectional"))
    )
    (net (code "26") (name "Net-(C23-P$2)") (class "Default")
      (node (ref "C23") (pin "2") (pinfunction "P$2_2") (pintype "bidirectional"))
      (node (ref "U6") (pin "44") (pinfunction "XTAL_N_44") (pintype "bidirectional"))
      (node (ref "Z1") (pin "3") (pinfunction "2_3") (pintype "passive"))
    )
    (net (code "27") (name "Net-(C24-P$2)") (class "Default")
      (node (ref "C24") (pin "2") (pinfunction "P$2_2") (pintype "bidirectional"))
      (node (ref "U6") (pin "45") (pinfunction "XTAL_P_45") (pintype "bidirectional"))
      (node (ref "Z1") (pin "1") (pinfunction "1_1") (pintype "passive"))
    )
    (net (code "28") (name "Net-(C25-P$2)") (class "Default")
      (node (ref "C25") (pin "2") (pinfunction "P$2_2") (pintype "bidirectional"))
      (node (ref "R20") (pin "2") (pinfunction "P$2_2") (pintype "bidirectional"))
      (node (ref "U3") (pin "3") (pinfunction "VCC_3") (pintype "bidirectional"))
    )
    (net (code "29") (name "Net-(C26-P$2)") (class "Default")
      (node (ref "C26") (pin "2") (pinfunction "P$2_2") (pintype "bidirectional"))
      (node (ref "R26") (pin "1") (pinfunction "P$1_1") (pintype "bidirectional"))
      (node (ref "S1") (pin "P$1") (pinfunction "3_P$1") (pintype "passive"))
      (node (ref "U6") (pin "10") (pinfunction "VDET_1_10") (pintype "bidirectional"))
    )
    (net (code "30") (name "Net-(C27-P$2)") (class "Default")
      (node (ref "C27") (pin "2") (pinfunction "P$2_2") (pintype "bidirectional"))
      (node (ref "R27") (pin "1") (pinfunction "P$1_1") (pintype "bidirectional"))
      (node (ref "S2") (pin "P$1") (pinfunction "3_P$1") (pintype "passive"))
      (node (ref "U6") (pin "8") (pinfunction "SENSOR_VN_8") (pintype "bidirectional"))
    )
    (net (code "31") (name "Net-(J1-1)") (class "Default")
      (node (ref "J1") (pin "P$1") (pinfunction "1_P$1") (pintype "passive"))
      (node (ref "R10") (pin "1") (pinfunction "P$1_1") (pintype "bidirectional"))
    )
    (net (code "32") (name "Net-(J2-1)") (class "Default")
      (node (ref "J2") (pin "P$1") (pinfunction "1_P$1") (pintype "passive"))
      (node (ref "R11") (pin "1") (pinfunction "P$1_1") (pintype "bidirectional"))
    )
    (net (code "33") (name "Net-(LED1-A)") (class "Default")
      (node (ref "LED1") (pin "2") (pinfunction "A_2") (pintype "passive"))
      (node (ref "R25") (pin "2") (pinfunction "P$2_2") (pintype "bidirectional"))
    )
    (net (code "34") (name "Net-(LED2-A)") (class "Default")
      (node (ref "LED2") (pin "2") (pinfunction "A_2") (pintype "passive"))
      (node (ref "R24") (pin "2") (pinfunction "P$2_2") (pintype "bidirectional"))
    )
    (net (code "35") (name "Net-(R3-P$2)") (class "Default")
      (node (ref "R3") (pin "2") (pinfunction "P$2_2") (pintype "bidirectional"))
      (node (ref "U1") (pin "EN/4") (pinfunction "EN_EN/4") (pintype "input"))
    )
    (net (code "36") (name "Net-(R4-P$1)") (class "Default")
      (node (ref "R4") (pin "1") (pinfunction "P$1_1") (pintype "bidirectional"))
      (node (ref "R5") (pin "2") (pinfunction "P$2_2") (pintype "bidirectional"))
      (node (ref "U1") (pin "FB/3") (pinfunction "FB_FB/3") (pintype "input"))
    )
    (net (code "37") (name "Net-(R8-P$2)") (class "Default")
      (node (ref "R8") (pin "2") (pinfunction "P$2_2") (pintype "bidirectional"))
      (node (ref "X8") (pin "1") (pinfunction "1_1") (pintype "passive"))
    )
    (net (code "38") (name "Net-(R12-P$2)") (class "Default")
      (node (ref "R12") (pin "2") (pinfunction "P$2_2") (pintype "bidirectional"))
      (node (ref "U6") (pin "18") (pinfunction "MTDI_18") (pintype "bidirectional"))
    )
    (net (code "39") (name "Net-(R13-P$2)") (class "Default")
      (node (ref "R13") (pin "2") (pinfunction "P$2_2") (pintype "bidirectional"))
      (node (ref "X7") (pin "1") (pinfunction "1_1") (pintype "passive"))
    )
    (net (code "40") (name "Net-(R14-P$2)") (class "Default")
      (node (ref "R14") (pin "2") (pinfunction "P$2_2") (pintype "bidirectional"))
      (node (ref "X6") (pin "1") (pinfunction "1_1") (pintype "passive"))
    )
    (net (code "41") (name "Net-(R15-P$2)") (class "Default")
      (node (ref "R15") (pin "2") (pinfunction "P$2_2") (pintype "bidirectional"))
      (node (ref "X5") (pin "1") (pinfunction "1_1") (pintype "passive"))
    )
    (net (code "42") (name "Net-(R16-P$2)") (class "Default")
      (node (ref "R16") (pin "2") (pinfunction "P$2_2") (pintype "bidirectional"))
      (node (ref "X4") (pin "1") (pinfunction "1_1") (pintype "passive"))
    )
    (net (code "43") (name "Net-(R17-P$2)") (class "Default")
      (node (ref "R17") (pin "2") (pinfunction "P$2_2") (pintype "bidirectional"))
      (node (ref "X3") (pin "1") (pinfunction "1_1") (pintype "passive"))
    )
    (net (code "44") (name "Net-(R18-P$2)") (class "Default")
      (node (ref "R18") (pin "2") (pinfunction "P$2_2") (pintype "bidirectional"))
      (node (ref "X9") (pin "3") (pinfunction "3_3") (pintype "passive"))
    )
    (net (code "45") (name "Net-(R19-P$2)") (class "Default")
      (node (ref "R19") (pin "2") (pinfunction "P$2_2") (pintype "bidirectional"))
      (node (ref "X9") (pin "2") (pinfunction "2_2") (pintype "passive"))
    )
    (net (code "46") (name "Net-(R22-P$1)") (class "Default")
      (node (ref "R22") (pin "1") (pinfunction "P$1_1") (pintype "bidirectional"))
      (node (ref "X11") (pin "3") (pinfunction "3_3") (pintype "passive"))
    )
    (net (code "47") (name "Net-(R23-P$1)") (class "Default")
      (node (ref "R23") (pin "1") (pinfunction "P$1_1") (pintype "bidirectional"))
      (node (ref "X11") (pin "2") (pinfunction "2_2") (pintype "passive"))
    )
    (net (code "48") (name "Net-(R24-P$1)") (class "Default")
      (node (ref "R24") (pin "1") (pinfunction "P$1_1") (pintype "bidirectional"))
      (node (ref "U6") (pin "22") (pinfunction "GPIO2_22") (pintype "bidirectional"))
    )
    (net (code "49") (name "Net-(R25-P$1)") (class "Default")
      (node (ref "R25") (pin "1") (pinfunction "P$1_1") (pintype "bidirectional"))
      (node (ref "U6") (pin "21") (pinfunction "MTDO_21") (pintype "bidirectional"))
    )
    (net (code "50") (name "Net-(R28-P$2)") (class "Default")
      (node (ref "R28") (pin "2") (pinfunction "P$2_2") (pintype "bidirectional"))
      (node (ref "VT5") (pin "3") (pinfunction "C_3") (pintype "passive"))
    )
    (net (code "51") (name "Net-(R29-P$2)") (class "Default")
      (node (ref "R29") (pin "2") (pinfunction "P$2_2") (pintype "bidirectional"))
      (node (ref "VT6") (pin "3") (pinfunction "C_3") (pintype "passive"))
    )
    (net (code "52") (name "Net-(R30-P$1)") (class "Default")
      (node (ref "R30") (pin "1") (pinfunction "P$1_1") (pintype "bidirectional"))
      (node (ref "X12") (pin "2") (pinfunction "2_2") (pintype "passive"))
    )
    (net (code "53") (name "Net-(R31-P$2)") (class "Default")
      (node (ref "R31") (pin "2") (pinfunction "P$2_2") (pintype "bidirectional"))
      (node (ref "R34") (pin "1") (pinfunction "P$1_1") (pintype "bidirectional"))
      (node (ref "VT1") (pin "3") (pinfunction "D_3") (pintype "passive"))
    )
    (net (code "54") (name "Net-(R32-P$2)") (class "Default")
      (node (ref "R32") (pin "2") (pinfunction "P$2_2") (pintype "bidirectional"))
      (node (ref "R33") (pin "2") (pinfunction "P$2_2") (pintype "bidirectional"))
      (node (ref "VT1") (pin "1") (pinfunction "G_1") (pintype "passive"))
    )
    (net (code "55") (name "Net-(R34-P$2)") (class "Default")
      (node (ref "R34") (pin "2") (pinfunction "P$2_2") (pintype "bidirectional"))
      (node (ref "VT2") (pin "1") (pinfunction "G_1") (pintype "passive"))
    )
    (net (code "56") (name "Net-(R35-P$2)") (class "Default")
      (node (ref "R35") (pin "2") (pinfunction "P$2_2") (pintype "bidirectional"))
      (node (ref "X9") (pin "4") (pinfunction "4_4") (pintype "passive"))
    )
    (net (code "57") (name "Net-(R38-P$2)") (class "Default")
      (node (ref "R38") (pin "2") (pinfunction "P$2_2") (pintype "bidirectional"))
      (node (ref "RX") (pin "P$1") (pinfunction "C_P$1") (pintype "passive"))
    )
    (net (code "58") (name "Net-(R39-P$2)") (class "Default")
      (node (ref "R39") (pin "2") (pinfunction "P$2_2") (pintype "bidirectional"))
      (node (ref "TX") (pin "P$1") (pinfunction "C_P$1") (pintype "passive"))
    )
    (net (code "59") (name "Net-(R40-P$1)") (class "Default")
      (node (ref "R40") (pin "1") (pinfunction "P$1_1") (pintype "bidirectional"))
      (node (ref "U10") (pin "14") (pinfunction "RTS_14") (pintype "bidirectional"))
      (node (ref "VT6") (pin "2") (pinfunction "E_2") (pintype "passive"))
    )
    (net (code "60") (name "Net-(R40-P$2)") (class "Default")
      (node (ref "R40") (pin "2") (pinfunction "P$2_2") (pintype "bidirectional"))
      (node (ref "VT5") (pin "1") (pinfunction "B_1") (pintype "passive"))
    )
    (net (code "61") (name "Net-(R41-P$1)") (class "Default")
      (node (ref "R41") (pin "1") (pinfunction "P$1_1") (pintype "bidirectional"))
      (node (ref "U10") (pin "13") (pinfunction "DTR_13") (pintype "bidirectional"))
      (node (ref "VT5") (pin "2") (pinfunction "E_2") (pintype "passive"))
    )
    (net (code "62") (name "Net-(R41-P$2)") (class "Default")
      (node (ref "R41") (pin "2") (pinfunction "P$2_2") (pintype "bidirectional"))
      (node (ref "VT6") (pin "1") (pinfunction "B_1") (pintype "passive"))
    )
    (net (code "63") (name "Net-(RAD1-ANTENNA)") (class "Default")
      (node (ref "J3") (pin "P$1") (pinfunction "P$1_P$1") (pintype "bidirectional"))
      (node (ref "RAD1") (pin "ANT") (pinfunction "ANTENNA_ANT") (pintype "passive"))
    )
    (net (code "64") (name "Net-(VD2-A)") (class "Default")
      (node (ref "VD2") (pin "1") (pinfunction "A_1") (pintype "passive"))
      (node (ref "X2") (pin "1") (pinfunction "5V_1") (pintype "passive"))
    )
    (net (code "65") (name "PWM1") (class "Default")
      (node (ref "R17") (pin "1") (pinfunction "P$1_1") (pintype "bidirectional"))
      (node (ref "U6") (pin "14") (pinfunction "GPIO25_14") (pintype "bidirectional"))
      (node (ref "VD3") (pin "3") (pinfunction "I/O_3") (pintype "bidirectional"))
    )
    (net (code "66") (name "PWM2") (class "Default")
      (node (ref "R16") (pin "1") (pinfunction "P$1_1") (pintype "bidirectional"))
      (node (ref "U6") (pin "13") (pinfunction "32K_XN_13") (pintype "bidirectional"))
      (node (ref "VD4") (pin "3") (pinfunction "I/O_3") (pintype "bidirectional"))
    )
    (net (code "67") (name "PWM3") (class "Default")
      (node (ref "R15") (pin "1") (pinfunction "P$1_1") (pintype "bidirectional"))
      (node (ref "U6") (pin "12") (pinfunction "32K_XP_12") (pintype "bidirectional"))
      (node (ref "VD5") (pin "3") (pinfunction "I/O_3") (pintype "bidirectional"))
    )
    (net (code "68") (name "PWM4") (class "Default")
      (node (ref "R14") (pin "1") (pinfunction "P$1_1") (pintype "bidirectional"))
      (node (ref "U6") (pin "20") (pinfunction "MTCK_20") (pintype "bidirectional"))
      (node (ref "VD6") (pin "3") (pinfunction "I/O_3") (pintype "bidirectional"))
    )
    (net (code "69") (name "PWM5") (class "Default")
      (node (ref "R13") (pin "1") (pinfunction "P$1_1") (pintype "bidirectional"))
      (node (ref "U6") (pin "16") (pinfunction "GPIO27_16") (pintype "bidirectional"))
      (node (ref "VD7") (pin "3") (pinfunction "I/O_3") (pintype "bidirectional"))
    )
    (net (code "70") (name "PWM6") (class "Default")
      (node (ref "R8") (pin "1") (pinfunction "P$1_1") (pintype "bidirectional"))
      (node (ref "U6") (pin "15") (pinfunction "GPIO26_15") (pintype "bidirectional"))
      (node (ref "VD8") (pin "3") (pinfunction "I/O_3") (pintype "bidirectional"))
    )
    (net (code "71") (name "RST") (class "Default")
      (node (ref "R10") (pin "2") (pinfunction "P$2_2") (pintype "bidirectional"))
      (node (ref "R29") (pin "1") (pinfunction "P$1_1") (pintype "bidirectional"))
      (node (ref "R9") (pin "1") (pinfunction "P$1_1") (pintype "bidirectional"))
      (node (ref "U6") (pin "9") (pinfunction "CHIP_PU_9") (pintype "bidirectional"))
    )
    (net (code "72") (name "RX") (class "Default")
      (node (ref "R38") (pin "1") (pinfunction "P$1_1") (pintype "bidirectional"))
      (node (ref "U10") (pin "3") (pinfunction "RX_3") (pintype "input"))
      (node (ref "U6") (pin "41") (pinfunction "U0TXD_41") (pintype "bidirectional"))
    )
    (net (code "73") (name "SBUS{slash}IBUS") (class "Default")
      (node (ref "R30") (pin "2") (pinfunction "P$2_2") (pintype "bidirectional"))
      (node (ref "U6") (pin "42") (pinfunction "GPIO21_42") (pintype "bidirectional"))
      (node (ref "VD11") (pin "3") (pinfunction "I/O_3") (pintype "bidirectional"))
    )
    (net (code "74") (name "SDI") (class "Default")
      (node (ref "U6") (pin "33") (pinfunction "SD_DATA_1_33") (pintype "bidirectional"))
      (node (ref "U7") (pin "P$6") (pinfunction "DIO_P$6") (pintype "bidirectional"))
    )
    (net (code "75") (name "SDO") (class "Default")
      (node (ref "U6") (pin "32") (pinfunction "SD_DATA_0_32") (pintype "bidirectional"))
      (node (ref "U7") (pin "P$3") (pinfunction "DO_P$3") (pintype "bidirectional"))
    )
    (net (code "76") (name "SHD") (class "Default")
      (node (ref "U6") (pin "28") (pinfunction "SD_DATA_2_28") (pintype "bidirectional"))
      (node (ref "U7") (pin "P$8") (pinfunction "HOLD_P$8") (pintype "bidirectional"))
    )
    (net (code "77") (name "STM_START") (class "Default")
      (node (ref "R32") (pin "1") (pinfunction "P$1_1") (pintype "bidirectional"))
      (node (ref "U6") (pin "17") (pinfunction "MTMS_17") (pintype "bidirectional"))
    )
    (net (code "78") (name "SWP") (class "Default")
      (node (ref "U6") (pin "29") (pinfunction "SD_DATA_3_29") (pintype "bidirectional"))
      (node (ref "U7") (pin "P$4") (pinfunction "WP_P$4") (pintype "bidirectional"))
    )
    (net (code "79") (name "TX") (class "Default")
      (node (ref "R39") (pin "1") (pinfunction "P$1_1") (pintype "bidirectional"))
      (node (ref "U10") (pin "2") (pinfunction "TX_2") (pintype "output"))
      (node (ref "U6") (pin "40") (pinfunction "U0RXD_40") (pintype "bidirectional"))
    )
    (net (code "80") (name "UART_RX") (class "Default")
      (node (ref "R19") (pin "1") (pinfunction "P$1_1") (pintype "bidirectional"))
      (node (ref "U6") (pin "25") (pinfunction "GPIO16_25") (pintype "bidirectional"))
    )
    (net (code "81") (name "UART_TX") (class "Default")
      (node (ref "R18") (pin "1") (pinfunction "P$1_1") (pintype "bidirectional"))
      (node (ref "U6") (pin "27") (pinfunction "GPIO17_27") (pintype "bidirectional"))
    )
    (net (code "82") (name "U_RX{slash}SDA") (class "Default")
      (node (ref "R23") (pin "2") (pinfunction "P$2_2") (pintype "bidirectional"))
      (node (ref "U6") (pin "35") (pinfunction "GPIO18_35") (pintype "bidirectional"))
      (node (ref "VD10") (pin "3") (pinfunction "I/O_3") (pintype "bidirectional"))
    )
    (net (code "83") (name "U_TX{slash}SCL") (class "Default")
      (node (ref "R22") (pin "2") (pinfunction "P$2_2") (pintype "bidirectional"))
      (node (ref "U6") (pin "38") (pinfunction "GPIO19_38") (pintype "bidirectional"))
      (node (ref "VD9") (pin "3") (pinfunction "I/O_3") (pintype "bidirectional"))
    )
    (net (code "84") (name "V_S") (class "Default")
      (node (ref "C28") (pin "2") (pinfunction "P$2_2") (pintype "bidirectional"))
      (node (ref "R1") (pin "1") (pinfunction "P$1_1") (pintype "bidirectional"))
      (node (ref "R2") (pin "2") (pinfunction "P$2_2") (pintype "bidirectional"))
      (node (ref "U6") (pin "5") (pinfunction "SENSOR_VP_5") (pintype "bidirectional"))
      (node (ref "VD1") (pin "2") (pinfunction "C_2") (pintype "passive"))
    )
    (net (code "85") (name "unconnected-(U2-NC-Pad4)") (class "Default")
      (node (ref "U2") (pin "4") (pinfunction "NC_4") (pintype "bidirectional"))
    )
    (net (code "86") (name "unconnected-(U3-LBK-Pad5)") (class "Default")
      (node (ref "U3") (pin "5") (pinfunction "LBK_5") (pintype "bidirectional"))
    )
    (net (code "87") (name "unconnected-(U6-GPIO5-Pad34)") (class "Default")
      (node (ref "U6") (pin "34") (pinfunction "GPIO5_34") (pintype "bidirectional"))
    )
    (net (code "88") (name "unconnected-(U6-SENSOR_CAPN-Pad7)") (class "Default")
      (node (ref "U6") (pin "7") (pinfunction "SENSOR_CAPN_7") (pintype "bidirectional"))
    )
    (net (code "89") (name "unconnected-(U6-SENSOR_CAPP-Pad6)") (class "Default")
      (node (ref "U6") (pin "6") (pinfunction "SENSOR_CAPP_6") (pintype "bidirectional"))
    )
    (net (code "90") (name "unconnected-(U6-VDET_2-Pad11)") (class "Default")
      (node (ref "U6") (pin "11") (pinfunction "VDET_2_11") (pintype "bidirectional"))
    )
    (net (code "91") (name "unconnected-(U10-CTS-Pad9)") (class "Default")
      (node (ref "U10") (pin "9") (pinfunction "CTS_9") (pintype "bidirectional"))
    )
    (net (code "92") (name "unconnected-(U10-DCD-Pad12)") (class "Default")
      (node (ref "U10") (pin "12") (pinfunction "DCD_12") (pintype "bidirectional"))
    )
    (net (code "93") (name "unconnected-(U10-DSR-Pad10)") (class "Default")
      (node (ref "U10") (pin "10") (pinfunction "DSR_10") (pintype "bidirectional"))
    )
    (net (code "94") (name "unconnected-(U10-R232-Pad15)") (class "Default")
      (node (ref "U10") (pin "15") (pinfunction "R232_15") (pintype "bidirectional"))
    )
    (net (code "95") (name "unconnected-(U10-RI-Pad11)") (class "Default")
      (node (ref "U10") (pin "11") (pinfunction "RI_11") (pintype "bidirectional"))
    )
    (net (code "96") (name "unconnected-(X2-ID-Pad4)") (class "Default")
      (node (ref "X2") (pin "4") (pinfunction "ID_4") (pintype "passive"))
    )
  )
)
